# 02.net
KiCad netlist of a schematic drawn in EasyEDA Pro
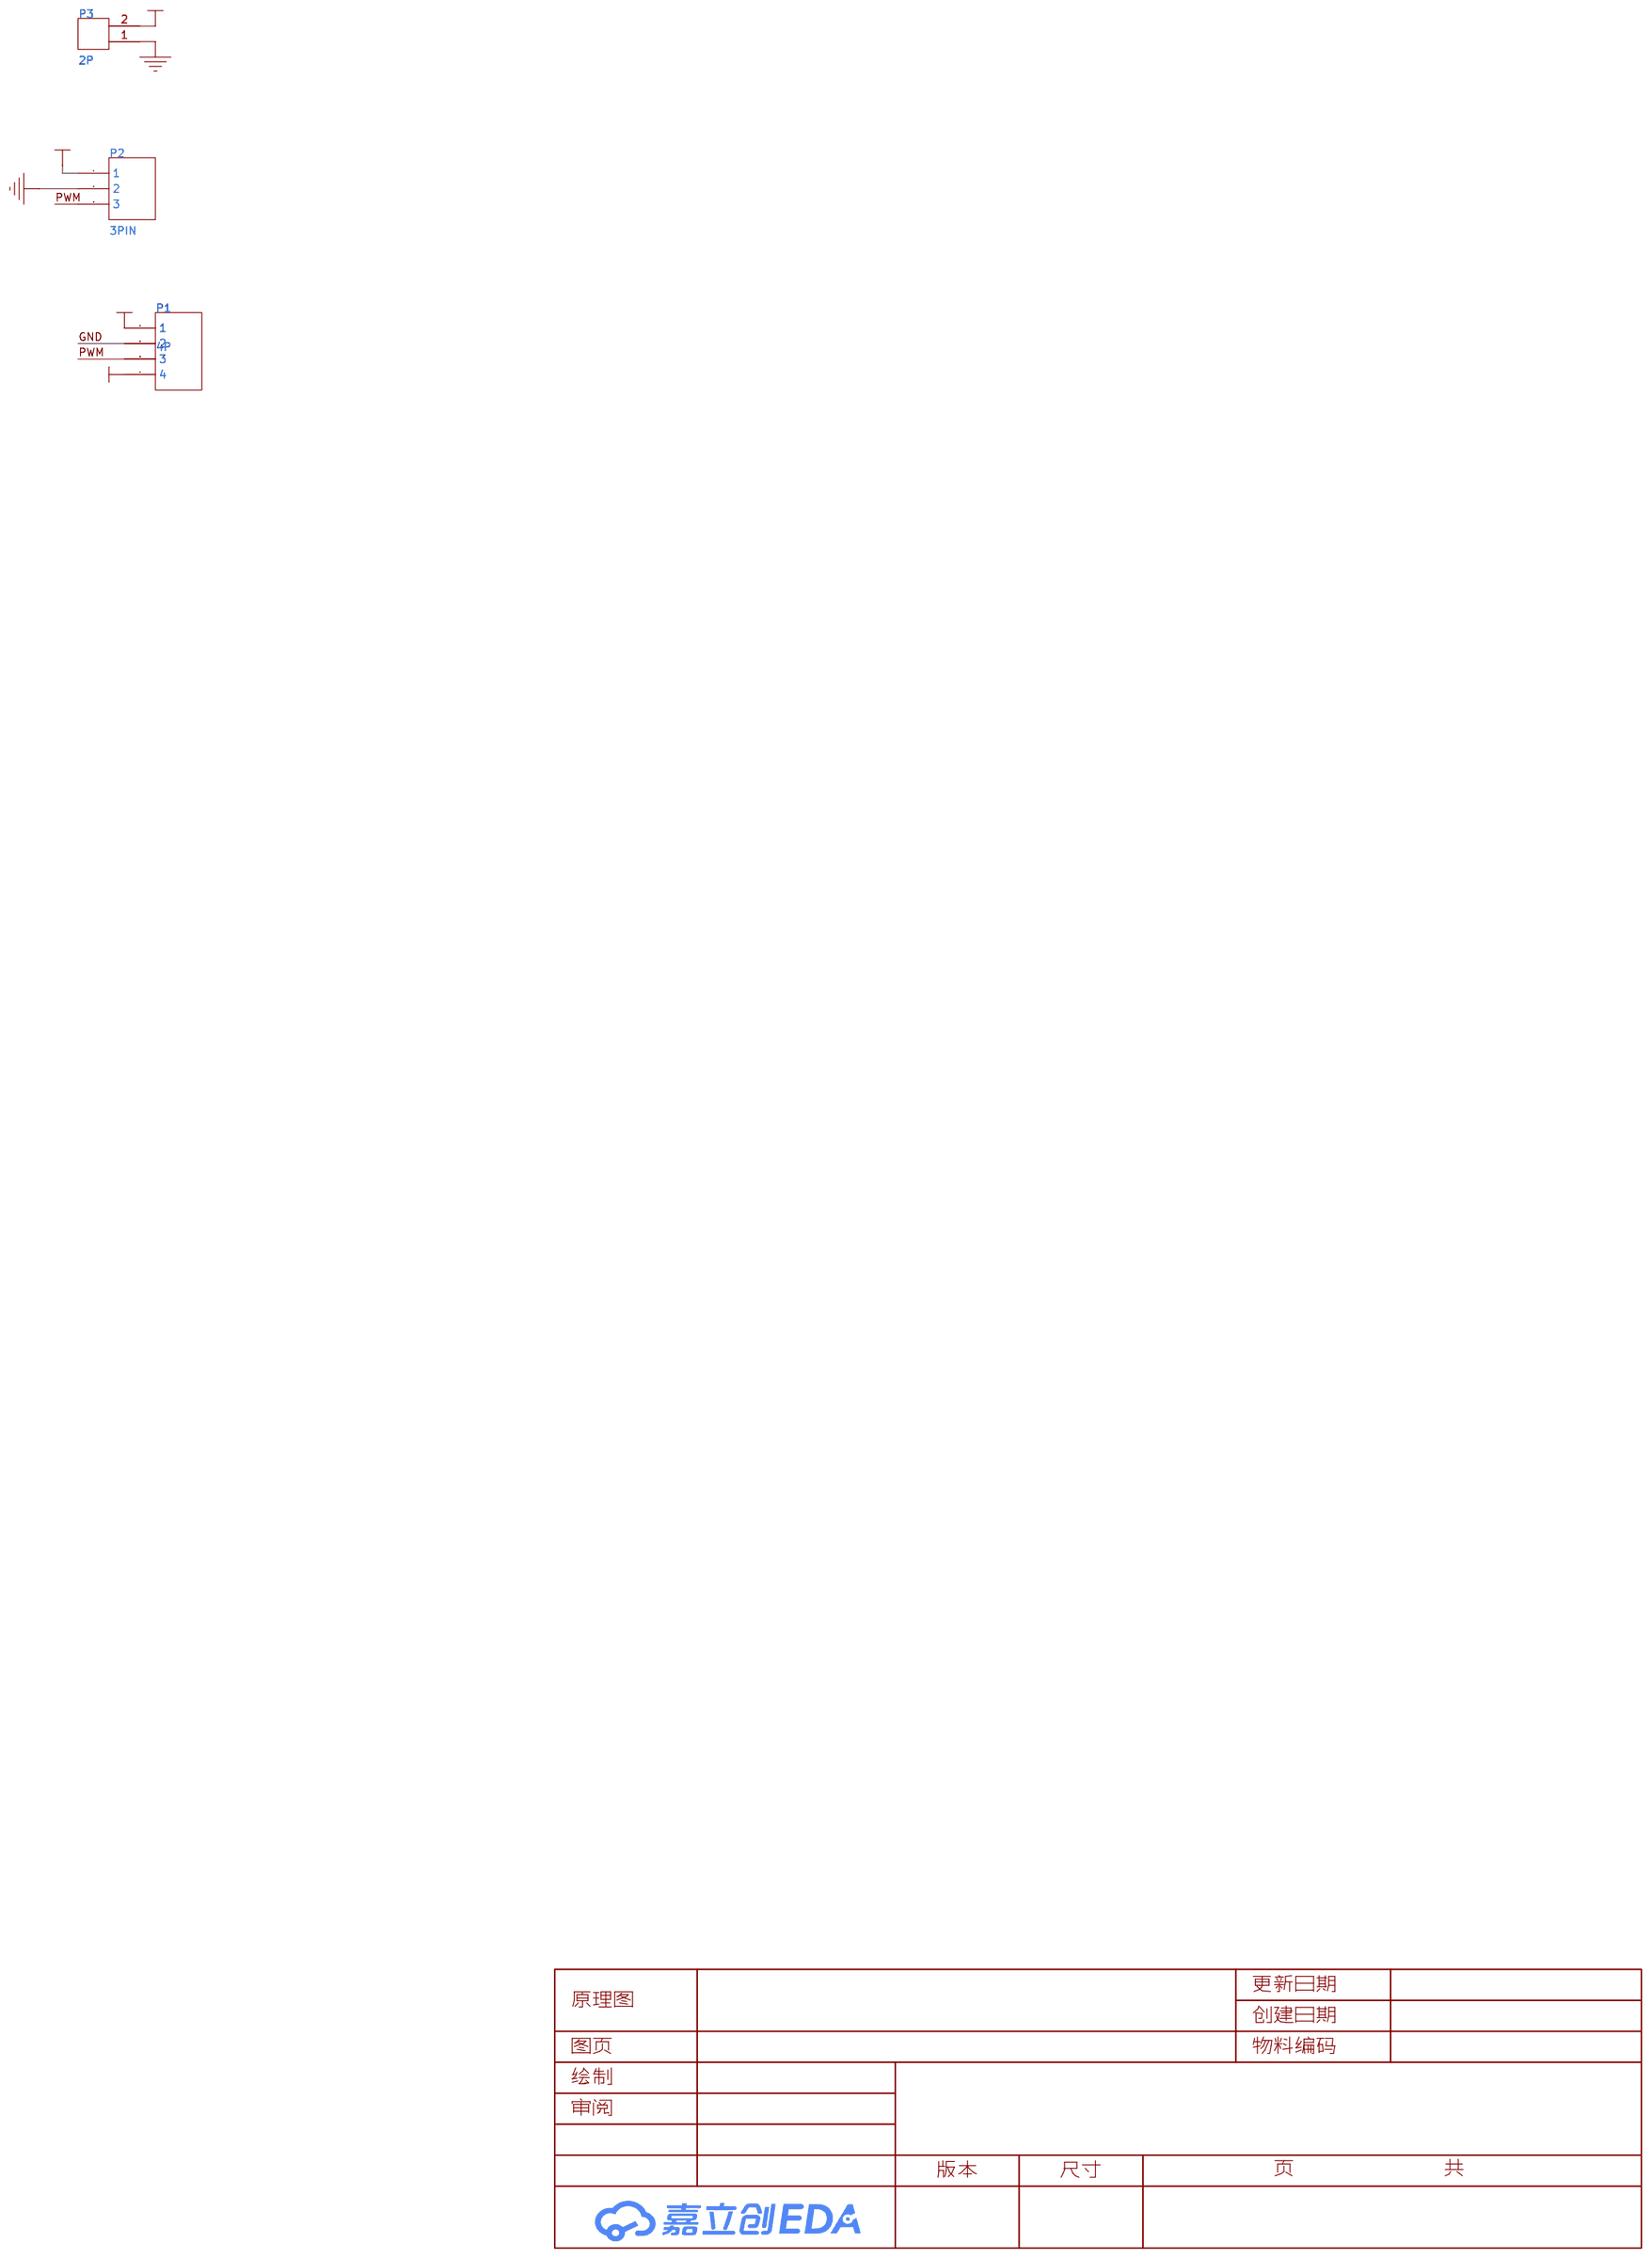
[diagram p0: schematic sheet]

(export (version "E")
  (design (tool "Eeschema 10.0.6"))
  (components
    (comp (ref "P1") (value "4P") (footprint "easyedapro:SIP4") (libsource (lib "easyedapro") (part "4P")))
    (comp (ref "P2")
      (value "3PIN")
      (footprint "easyedapro:HDR1X3_P")
      (libsource (lib "easyedapro") (part "3P"))
    )
    (comp (ref "P3")
      (value "2P")
      (footprint "easyedapro:HDR1X2_P")
      (libsource (lib "easyedapro") (part "2P"))
    )
  )
  (nets
    (net (code "1") (name "/PWM") (class "Default")
      (node (ref "P1") (pin "3") (pinfunction "3_3") (pintype "unspecified"))
      (node (ref "P2") (pin "3") (pinfunction "3_3") (pintype "unspecified"))
    )
    (net (code "2") (name "12V") (class "Default")
      (node (ref "P1") (pin "4") (pinfunction "4_4") (pintype "unspecified"))
      (node (ref "P2") (pin "1") (pinfunction "1_1") (pintype "unspecified"))
    )
    (net (code "3") (name "48V") (class "Default")
      (node (ref "P1") (pin "1") (pinfunction "1_1") (pintype "unspecified"))
      (node (ref "P3") (pin "2") (pintype "unspecified"))
    )
    (net (code "4") (name "GND") (class "Default")
      (node (ref "P1") (pin "2") (pinfunction "2_2") (pintype "unspecified"))
      (node (ref "P2") (pin "2") (pinfunction "2_2") (pintype "unspecified"))
      (node (ref "P3") (pin "1") (pintype "unspecified"))
    )
  )
)
